# electric-imp-version.net
KiCad netlist of a schematic drawn in EAGLE
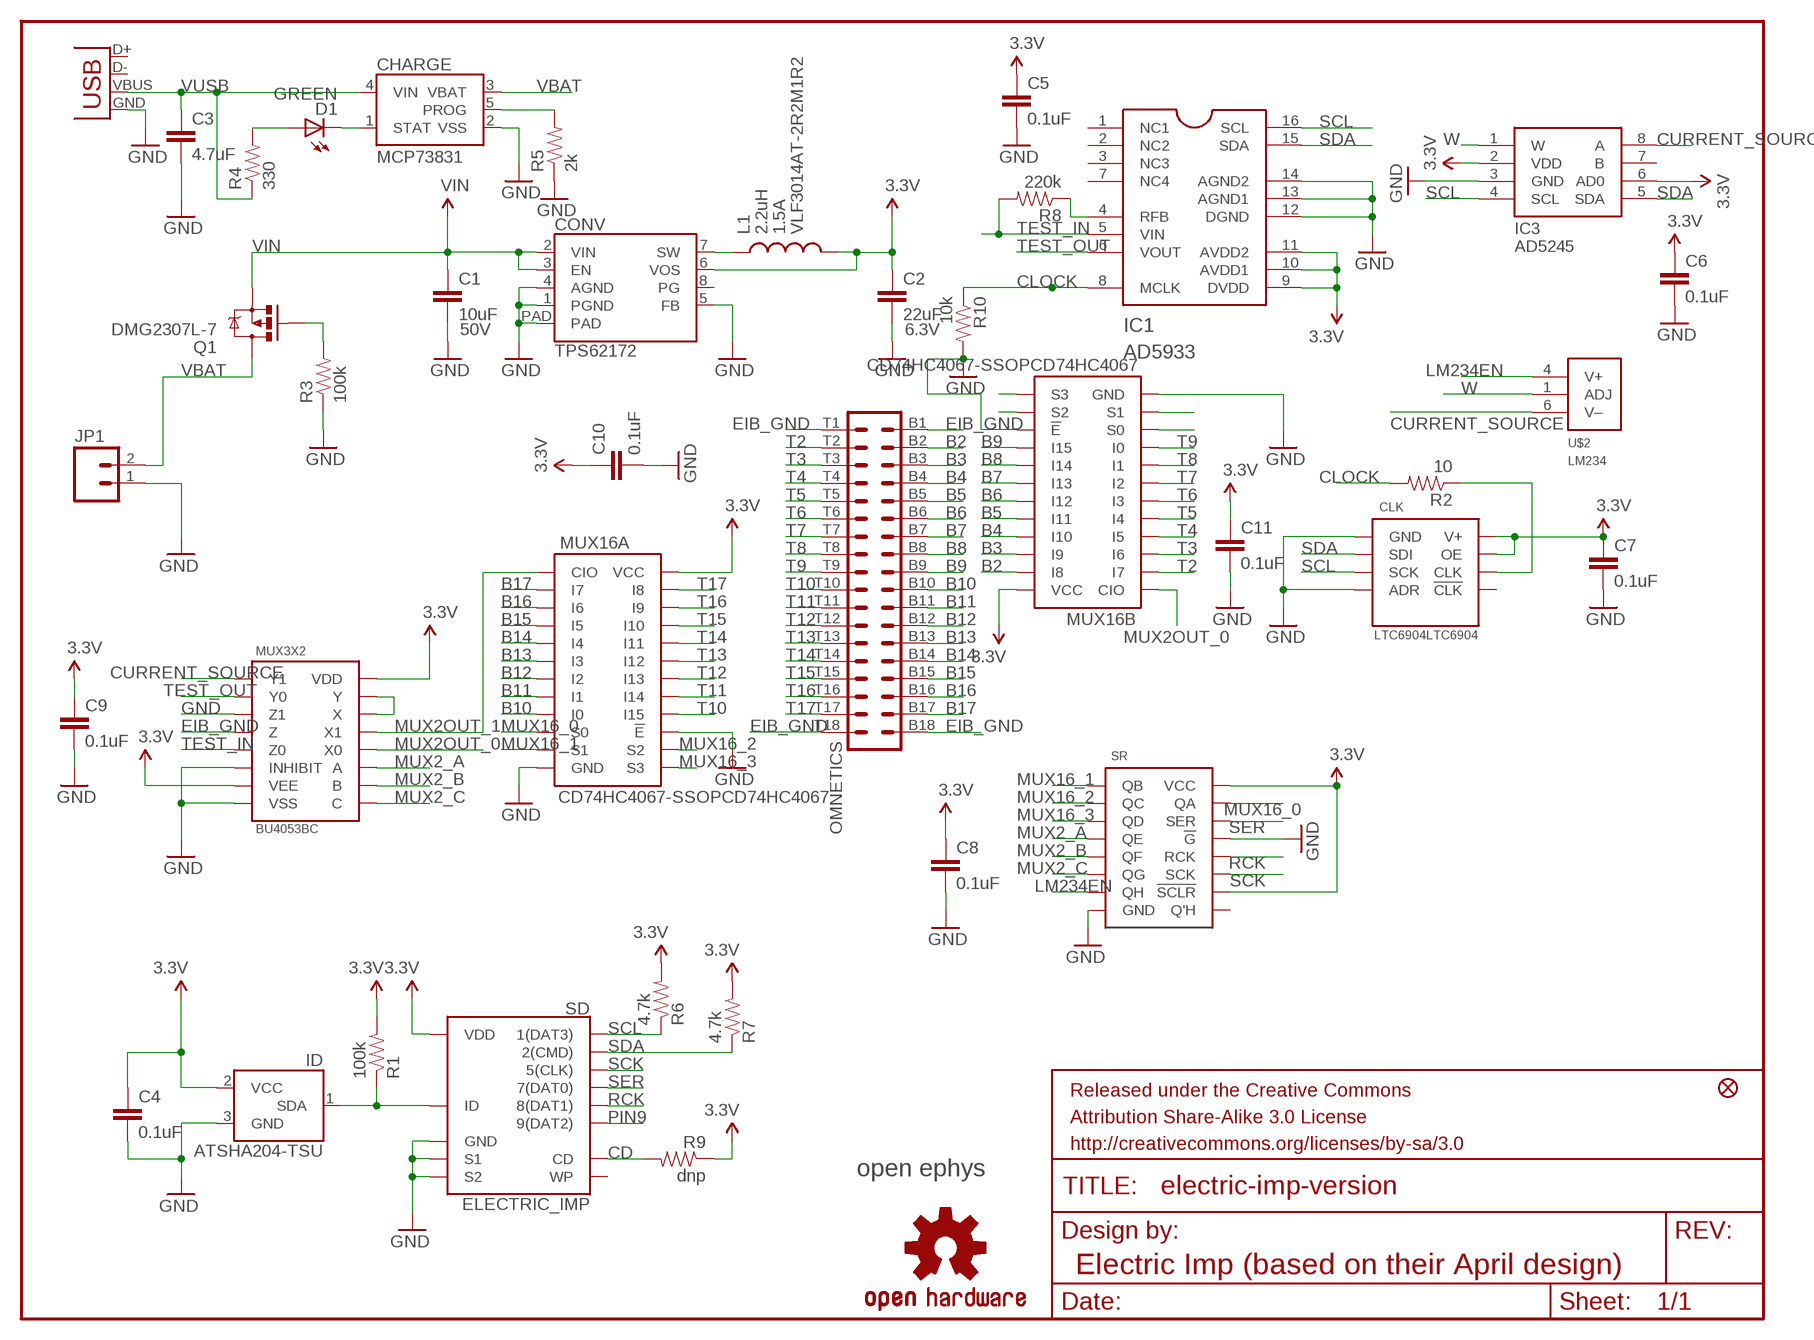
[diagram p0: schematic, sheet 1]

(export (version "E")
  (design (tool "Eeschema 10.0.6"))
  (components
    (comp (ref "C1")
      (value "10uF")
      (footprint "eagle-import:1210")
      (libsource (lib "eagle-import") (part "SparkFun-Passives_CAP1210"))
    )
    (comp (ref "C2")
      (value "22uF")
      (footprint "eagle-import:0805")
      (libsource (lib "eagle-import") (part "SparkFun-Passives_CAP0805"))
    )
    (comp (ref "C3")
      (value "4.7uF")
      (footprint "eagle-import:1210")
      (libsource (lib "eagle-import") (part "SparkFun-Passives_CAP1210"))
    )
    (comp (ref "C4")
      (value "0.1uF")
      (footprint "eagle-import:0603-CAP")
      (libsource (lib "eagle-import") (part "CAP0603-CAP"))
    )
    (comp (ref "C5")
      (value "0.1uF")
      (footprint "eagle-import:0603-CAP")
      (libsource (lib "eagle-import") (part "CAP0603-CAP"))
    )
    (comp (ref "C6")
      (value "0.1uF")
      (footprint "eagle-import:0603-CAP")
      (libsource (lib "eagle-import") (part "CAP0603-CAP"))
    )
    (comp (ref "C7")
      (value "0.1uF")
      (footprint "eagle-import:0603-CAP")
      (libsource (lib "eagle-import") (part "CAP0603-CAP"))
    )
    (comp (ref "C8")
      (value "0.1uF")
      (footprint "eagle-import:0603-CAP")
      (libsource (lib "eagle-import") (part "CAP0603-CAP"))
    )
    (comp (ref "C9")
      (value "0.1uF")
      (footprint "eagle-import:0603-CAP")
      (libsource (lib "eagle-import") (part "CAP0603-CAP"))
    )
    (comp (ref "C10")
      (value "0.1uF")
      (footprint "eagle-import:0603-CAP")
      (libsource (lib "eagle-import") (part "CAP0603-CAP"))
    )
    (comp (ref "C11")
      (value "0.1uF")
      (footprint "eagle-import:0603-CAP")
      (libsource (lib "eagle-import") (part "CAP0603-CAP"))
    )
    (comp (ref "CHARGE")
      (value "MCP73831")
      (footprint "eagle-import:SOT23-5")
      (libsource (lib "eagle-import") (part "MCP73831"))
    )
    (comp (ref "CLK")
      (value "LTC6904LTC6904")
      (footprint "eagle-import:MSOP08")
      (libsource (lib "eagle-import") (part "LTC6904LTC6904"))
    )
    (comp (ref "CONV")
      (value "TPS62172")
      (footprint "eagle-import:WSON-8-PAD")
      (libsource (lib "eagle-import") (part "TPS62172"))
    )
    (comp (ref "D1")
      (value "GREEN")
      (footprint "eagle-import:LED-0603")
      (libsource (lib "eagle-import") (part "LED-GREEN0603"))
    )
    (comp (ref "FRAME1")
      (value "FRAME-LETTER")
      (footprint "eagle-import:CREATIVE_COMMONS")
      (libsource (lib "eagle-import") (part "FRAME-LETTER"))
    )
    (comp (ref "IC1")
      (value "AD5933")
      (footprint "eagle-import:AD5933")
      (libsource (lib "eagle-import") (part "AD5933"))
    )
    (comp (ref "IC3")
      (value "AD5245")
      (footprint "eagle-import:AD5245")
      (libsource (lib "eagle-import") (part "AD5245"))
    )
    (comp (ref "ID")
      (value "ATSHA204-TSU")
      (footprint "eagle-import:SOT23-3")
      (libsource (lib "eagle-import") (part "ATSHA204-TSU"))
    )
    (comp (ref "JP1")
      (value "M02SMD")
      (footprint "eagle-import:1X02_SMD")
      (libsource (lib "eagle-import") (part "M02SMD"))
    )
    (comp (ref "JP8")
      (value "FIDUCIALUFIDUCIAL")
      (footprint "eagle-import:MICRO-FIDUCIAL")
      (libsource (lib "eagle-import") (part "FIDUCIALUFIDUCIAL"))
    )
    (comp (ref "L1")
      (value "2.2uH")
      (footprint "eagle-import:VLF4012A")
      (libsource (lib "eagle-import") (part "INDUCTORVLF4012A"))
    )
    (comp (ref "MUX3X2")
      (value "BU4053BC")
      (footprint "eagle-import:SSOP16")
      (libsource (lib "eagle-import") (part "BU4053BC"))
    )
    (comp (ref "MUX16A")
      (value "CD74HC4067-SSOPCD74HC4067")
      (footprint "eagle-import:SSOP24")
      (libsource (lib "eagle-import") (part "CD74HC4067-SSOPCD74HC4067"))
    )
    (comp (ref "MUX16B")
      (value "CD74HC4067-SSOPCD74HC4067")
      (footprint "eagle-import:SSOP24")
      (libsource (lib "eagle-import") (part "CD74HC4067-SSOPCD74HC4067"))
    )
    (comp (ref "OMNETICS")
      (value "OMNETICS_A79025")
      (footprint "eagle-import:OMNETICS_A79025")
      (libsource (lib "eagle-import") (part "OMNETICS_A79025"))
    )
    (comp (ref "Q1")
      (value "DMG2307L-7")
      (footprint "eagle-import:SOT23-3")
      (libsource (lib "eagle-import") (part "MOSFET-PCHANNELSMD"))
    )
    (comp (ref "R1")
      (value "100k")
      (footprint "eagle-import:0402-RES")
      (libsource (lib "eagle-import") (part "RESISTOR0402-RES"))
    )
    (comp (ref "R2")
      (value "10")
      (footprint "eagle-import:0402-RES")
      (libsource (lib "eagle-import") (part "RESISTOR0402-RES"))
    )
    (comp (ref "R3")
      (value "100k")
      (footprint "eagle-import:0402-RES")
      (libsource (lib "eagle-import") (part "RESISTOR0402-RES"))
    )
    (comp (ref "R4")
      (value "330")
      (footprint "eagle-import:0402-RES")
      (libsource (lib "eagle-import") (part "RESISTOR0402-RES"))
    )
    (comp (ref "R5")
      (value "2k")
      (footprint "eagle-import:0402-RES")
      (libsource (lib "eagle-import") (part "RESISTOR0402-RES"))
    )
    (comp (ref "R6")
      (value "4.7k")
      (footprint "eagle-import:0402-RES")
      (libsource (lib "eagle-import") (part "RESISTOR0402-RES"))
    )
    (comp (ref "R7")
      (value "4.7k")
      (footprint "eagle-import:0402-RES")
      (libsource (lib "eagle-import") (part "RESISTOR0402-RES"))
    )
    (comp (ref "R8")
      (value "220k")
      (footprint "eagle-import:0402-RES")
      (libsource (lib "eagle-import") (part "RESISTOR0402-RES"))
    )
    (comp (ref "R9")
      (value "dnp")
      (footprint "eagle-import:0402-RES")
      (libsource (lib "eagle-import") (part "RESISTOR0402-RES"))
    )
    (comp (ref "R10")
      (value "10k")
      (footprint "eagle-import:0402-RES")
      (libsource (lib "eagle-import") (part "RESISTOR0402-RES"))
    )
    (comp (ref "SD")
      (value "ELECTRIC_IMP")
      (footprint "eagle-import:SD_MMC_SOCKET")
      (libsource (lib "eagle-import") (part "ELECTRIC_IMP"))
    )
    (comp (ref "SR")
      (value "MM74HC595MM74HC595")
      (footprint "eagle-import:TSSOP16")
      (libsource (lib "eagle-import") (part "MM74HC595MM74HC595"))
    )
    (comp (ref "U$2")
      (value "LM234")
      (footprint "eagle-import:LM234")
      (libsource (lib "eagle-import") (part "LM234"))
    )
    (comp (ref "U$5")
      (value "OSHW-LOGOS")
      (footprint "eagle-import:OSHW-LOGO-S")
      (libsource (lib "eagle-import") (part "OSHW-LOGOS"))
    )
    (comp (ref "U$7")
      (value "OPEN_EPHYS_LOGO")
      (footprint "eagle-import:OPEN_EPHYS_LOGO")
      (libsource (lib "eagle-import") (part "OPEN_EPHYS_LOGO"))
    )
    (comp (ref "USB")
      (value "USBSMD")
      (footprint "eagle-import:USB-MINIB")
      (libsource (lib "eagle-import") (part "USBSMD"))
    )
  )
  (nets
    (net (code "1") (name "/B2") (class "Default")
      (node (ref "MUX16B") (pin "23") (pinfunction "I8_23") (pintype "bidirectional"))
      (node (ref "OMNETICS") (pin "B2") (pinfunction "B2_B2") (pintype "passive"))
    )
    (net (code "2") (name "/B3") (class "Default")
      (node (ref "MUX16B") (pin "22") (pinfunction "I9_22") (pintype "bidirectional"))
      (node (ref "OMNETICS") (pin "B3") (pinfunction "B3_B3") (pintype "passive"))
    )
    (net (code "3") (name "/B4") (class "Default")
      (node (ref "MUX16B") (pin "21") (pinfunction "I10_21") (pintype "bidirectional"))
      (node (ref "OMNETICS") (pin "B4") (pinfunction "B4_B4") (pintype "passive"))
    )
    (net (code "4") (name "/B5") (class "Default")
      (node (ref "MUX16B") (pin "20") (pinfunction "I11_20") (pintype "bidirectional"))
      (node (ref "OMNETICS") (pin "B5") (pinfunction "B5_B5") (pintype "passive"))
    )
    (net (code "5") (name "/B6") (class "Default")
      (node (ref "MUX16B") (pin "19") (pinfunction "I12_19") (pintype "bidirectional"))
      (node (ref "OMNETICS") (pin "B6") (pinfunction "B6_B6") (pintype "passive"))
    )
    (net (code "6") (name "/B7") (class "Default")
      (node (ref "MUX16B") (pin "18") (pinfunction "I13_18") (pintype "bidirectional"))
      (node (ref "OMNETICS") (pin "B7") (pinfunction "B7_B7") (pintype "passive"))
    )
    (net (code "7") (name "/B8") (class "Default")
      (node (ref "MUX16B") (pin "17") (pinfunction "I14_17") (pintype "bidirectional"))
      (node (ref "OMNETICS") (pin "B8") (pinfunction "B8_B8") (pintype "passive"))
    )
    (net (code "8") (name "/B9") (class "Default")
      (node (ref "MUX16B") (pin "16") (pinfunction "I15_16") (pintype "bidirectional"))
      (node (ref "OMNETICS") (pin "B9") (pinfunction "B9_B9") (pintype "passive"))
    )
    (net (code "9") (name "/B10") (class "Default")
      (node (ref "MUX16A") (pin "9") (pinfunction "I0_9") (pintype "bidirectional"))
      (node (ref "OMNETICS") (pin "B10") (pinfunction "B10_B10") (pintype "passive"))
    )
    (net (code "10") (name "/B11") (class "Default")
      (node (ref "MUX16A") (pin "8") (pinfunction "I1_8") (pintype "bidirectional"))
      (node (ref "OMNETICS") (pin "B11") (pinfunction "B11_B11") (pintype "passive"))
    )
    (net (code "11") (name "/B12") (class "Default")
      (node (ref "MUX16A") (pin "7") (pinfunction "I2_7") (pintype "bidirectional"))
      (node (ref "OMNETICS") (pin "B12") (pinfunction "B12_B12") (pintype "passive"))
    )
    (net (code "12") (name "/B13") (class "Default")
      (node (ref "MUX16A") (pin "6") (pinfunction "I3_6") (pintype "bidirectional"))
      (node (ref "OMNETICS") (pin "B13") (pinfunction "B13_B13") (pintype "passive"))
    )
    (net (code "13") (name "/B14") (class "Default")
      (node (ref "MUX16A") (pin "5") (pinfunction "I4_5") (pintype "bidirectional"))
      (node (ref "OMNETICS") (pin "B14") (pinfunction "B14_B14") (pintype "passive"))
    )
    (net (code "14") (name "/B15") (class "Default")
      (node (ref "MUX16A") (pin "4") (pinfunction "I5_4") (pintype "bidirectional"))
      (node (ref "OMNETICS") (pin "B15") (pinfunction "B15_B15") (pintype "passive"))
    )
    (net (code "15") (name "/B16") (class "Default")
      (node (ref "MUX16A") (pin "3") (pinfunction "I6_3") (pintype "bidirectional"))
      (node (ref "OMNETICS") (pin "B16") (pinfunction "B16_B16") (pintype "passive"))
    )
    (net (code "16") (name "/B17") (class "Default")
      (node (ref "MUX16A") (pin "2") (pinfunction "I7_2") (pintype "bidirectional"))
      (node (ref "OMNETICS") (pin "B17") (pinfunction "B17_B17") (pintype "passive"))
    )
    (net (code "17") (name "/CD") (class "Default")
      (node (ref "R9") (pin "2") (pinfunction "2_2") (pintype "passive"))
      (node (ref "SD") (pin "CD") (pinfunction "CD_CD") (pintype "bidirectional"))
    )
    (net (code "18") (name "/CLOCK") (class "Default")
      (node (ref "IC1") (pin "8") (pinfunction "MCLK_8") (pintype "bidirectional"))
      (node (ref "R10") (pin "1") (pinfunction "1_1") (pintype "passive"))
      (node (ref "R2") (pin "2") (pinfunction "2_2") (pintype "passive"))
    )
    (net (code "19") (name "/CURRENT_SOURCE") (class "Default")
      (node (ref "IC3") (pin "8") (pinfunction "A_8") (pintype "bidirectional"))
      (node (ref "MUX3X2") (pin "1") (pinfunction "Y1_1") (pintype "bidirectional"))
      (node (ref "U$2") (pin "6") (pinfunction "V–_6") (pintype "bidirectional"))
    )
    (net (code "20") (name "/EIB_GND") (class "Default")
      (node (ref "MUX3X2") (pin "4") (pinfunction "Z_4") (pintype "bidirectional"))
      (node (ref "OMNETICS") (pin "B1") (pinfunction "B1_B1") (pintype "passive"))
      (node (ref "OMNETICS") (pin "B18") (pinfunction "B18_B18") (pintype "passive"))
      (node (ref "OMNETICS") (pin "T1") (pinfunction "T1_T1") (pintype "passive"))
      (node (ref "OMNETICS") (pin "T18") (pinfunction "T18_T18") (pintype "passive"))
    )
    (net (code "21") (name "/LM234EN") (class "Default")
      (node (ref "SR") (pin "7") (pinfunction "QH_7") (pintype "output"))
      (node (ref "U$2") (pin "4") (pinfunction "V+_4") (pintype "bidirectional"))
    )
    (net (code "22") (name "/MUX2OUT_0") (class "Default")
      (node (ref "MUX16B") (pin "1") (pinfunction "CIO_1") (pintype "bidirectional"))
      (node (ref "MUX3X2") (pin "12") (pinfunction "X0_12") (pintype "bidirectional"))
    )
    (net (code "23") (name "/MUX2OUT_1") (class "Default")
      (node (ref "MUX16A") (pin "1") (pinfunction "CIO_1") (pintype "bidirectional"))
      (node (ref "MUX3X2") (pin "13") (pinfunction "X1_13") (pintype "bidirectional"))
    )
    (net (code "24") (name "/MUX2_A") (class "Default")
      (node (ref "MUX3X2") (pin "11") (pinfunction "A_11") (pintype "bidirectional"))
      (node (ref "SR") (pin "4") (pinfunction "QE_4") (pintype "output"))
    )
    (net (code "25") (name "/MUX2_B") (class "Default")
      (node (ref "MUX3X2") (pin "10") (pinfunction "B_10") (pintype "bidirectional"))
      (node (ref "SR") (pin "5") (pinfunction "QF_5") (pintype "output"))
    )
    (net (code "26") (name "/MUX2_C") (class "Default")
      (node (ref "MUX3X2") (pin "9") (pinfunction "C_9") (pintype "power_in"))
      (node (ref "SR") (pin "6") (pinfunction "QG_6") (pintype "output"))
    )
    (net (code "27") (name "/MUX16_0") (class "Default")
      (node (ref "MUX16A") (pin "10") (pinfunction "S0_10") (pintype "bidirectional"))
      (node (ref "MUX16B") (pin "10") (pinfunction "S0_10") (pintype "bidirectional"))
      (node (ref "SR") (pin "15") (pinfunction "QA_15") (pintype "output"))
    )
    (net (code "28") (name "/MUX16_1") (class "Default")
      (node (ref "MUX16A") (pin "11") (pinfunction "S1_11") (pintype "bidirectional"))
      (node (ref "MUX16B") (pin "11") (pinfunction "S1_11") (pintype "bidirectional"))
      (node (ref "SR") (pin "1") (pinfunction "QB_1") (pintype "output"))
    )
    (net (code "29") (name "/MUX16_2") (class "Default")
      (node (ref "MUX16A") (pin "14") (pinfunction "S2_14") (pintype "bidirectional"))
      (node (ref "MUX16B") (pin "14") (pinfunction "S2_14") (pintype "bidirectional"))
      (node (ref "SR") (pin "2") (pinfunction "QC_2") (pintype "output"))
    )
    (net (code "30") (name "/MUX16_3") (class "Default")
      (node (ref "MUX16A") (pin "13") (pinfunction "S3_13") (pintype "bidirectional"))
      (node (ref "MUX16B") (pin "13") (pinfunction "S3_13") (pintype "bidirectional"))
      (node (ref "SR") (pin "3") (pinfunction "QD_3") (pintype "output"))
    )
    (net (code "31") (name "/PIN9") (class "Default")
      (node (ref "SD") (pin "9") (pinfunction "9(DAT2)_9") (pintype "bidirectional"))
    )
    (net (code "32") (name "/RCK") (class "Default")
      (node (ref "SD") (pin "8") (pinfunction "8(DAT1)_8") (pintype "bidirectional"))
      (node (ref "SR") (pin "12") (pinfunction "RCK_12") (pintype "input"))
    )
    (net (code "33") (name "/SCK") (class "Default")
      (node (ref "SD") (pin "5") (pinfunction "5(CLK)_5") (pintype "bidirectional"))
      (node (ref "SR") (pin "11") (pinfunction "SCK_11") (pintype "input"))
    )
    (net (code "34") (name "/SCL") (class "Default")
      (node (ref "CLK") (pin "3") (pinfunction "SCK_3") (pintype "input"))
      (node (ref "IC1") (pin "16") (pinfunction "SCL_16") (pintype "bidirectional"))
      (node (ref "IC3") (pin "4") (pinfunction "SCL_4") (pintype "bidirectional"))
      (node (ref "R6") (pin "1") (pinfunction "1_1") (pintype "passive"))
      (node (ref "SD") (pin "1") (pinfunction "1(DAT3)_1") (pintype "bidirectional"))
    )
    (net (code "35") (name "/SDA") (class "Default")
      (node (ref "CLK") (pin "2") (pinfunction "SDI_2") (pintype "input"))
      (node (ref "IC1") (pin "15") (pinfunction "SDA_15") (pintype "bidirectional"))
      (node (ref "IC3") (pin "5") (pinfunction "SDA_5") (pintype "bidirectional"))
      (node (ref "R7") (pin "1") (pinfunction "1_1") (pintype "passive"))
      (node (ref "SD") (pin "2") (pinfunction "2(CMD)_2") (pintype "bidirectional"))
    )
    (net (code "36") (name "/SER") (class "Default")
      (node (ref "SD") (pin "7") (pinfunction "7(DAT0)_7") (pintype "bidirectional"))
      (node (ref "SR") (pin "14") (pinfunction "SER_14") (pintype "input"))
    )
    (net (code "37") (name "/T2") (class "Default")
      (node (ref "MUX16B") (pin "2") (pinfunction "I7_2") (pintype "bidirectional"))
      (node (ref "OMNETICS") (pin "T2") (pinfunction "T2_T2") (pintype "passive"))
    )
    (net (code "38") (name "/T3") (class "Default")
      (node (ref "MUX16B") (pin "3") (pinfunction "I6_3") (pintype "bidirectional"))
      (node (ref "OMNETICS") (pin "T3") (pinfunction "T3_T3") (pintype "passive"))
    )
    (net (code "39") (name "/T4") (class "Default")
      (node (ref "MUX16B") (pin "4") (pinfunction "I5_4") (pintype "bidirectional"))
      (node (ref "OMNETICS") (pin "T4") (pinfunction "T4_T4") (pintype "passive"))
    )
    (net (code "40") (name "/T5") (class "Default")
      (node (ref "MUX16B") (pin "5") (pinfunction "I4_5") (pintype "bidirectional"))
      (node (ref "OMNETICS") (pin "T5") (pinfunction "T5_T5") (pintype "passive"))
    )
    (net (code "41") (name "/T6") (class "Default")
      (node (ref "MUX16B") (pin "6") (pinfunction "I3_6") (pintype "bidirectional"))
      (node (ref "OMNETICS") (pin "T6") (pinfunction "T6_T6") (pintype "passive"))
    )
    (net (code "42") (name "/T7") (class "Default")
      (node (ref "MUX16B") (pin "7") (pinfunction "I2_7") (pintype "bidirectional"))
      (node (ref "OMNETICS") (pin "T7") (pinfunction "T7_T7") (pintype "passive"))
    )
    (net (code "43") (name "/T8") (class "Default")
      (node (ref "MUX16B") (pin "8") (pinfunction "I1_8") (pintype "bidirectional"))
      (node (ref "OMNETICS") (pin "T8") (pinfunction "T8_T8") (pintype "passive"))
    )
    (net (code "44") (name "/T9") (class "Default")
      (node (ref "MUX16B") (pin "9") (pinfunction "I0_9") (pintype "bidirectional"))
      (node (ref "OMNETICS") (pin "T9") (pinfunction "T9_T9") (pintype "passive"))
    )
    (net (code "45") (name "/T10") (class "Default")
      (node (ref "MUX16A") (pin "16") (pinfunction "I15_16") (pintype "bidirectional"))
      (node (ref "OMNETICS") (pin "T10") (pinfunction "T10_T10") (pintype "passive"))
    )
    (net (code "46") (name "/T11") (class "Default")
      (node (ref "MUX16A") (pin "17") (pinfunction "I14_17") (pintype "bidirectional"))
      (node (ref "OMNETICS") (pin "T11") (pinfunction "T11_T11") (pintype "passive"))
    )
    (net (code "47") (name "/T12") (class "Default")
      (node (ref "MUX16A") (pin "18") (pinfunction "I13_18") (pintype "bidirectional"))
      (node (ref "OMNETICS") (pin "T12") (pinfunction "T12_T12") (pintype "passive"))
    )
    (net (code "48") (name "/T13") (class "Default")
      (node (ref "MUX16A") (pin "19") (pinfunction "I12_19") (pintype "bidirectional"))
      (node (ref "OMNETICS") (pin "T13") (pinfunction "T13_T13") (pintype "passive"))
    )
    (net (code "49") (name "/T14") (class "Default")
      (node (ref "MUX16A") (pin "20") (pinfunction "I11_20") (pintype "bidirectional"))
      (node (ref "OMNETICS") (pin "T14") (pinfunction "T14_T14") (pintype "passive"))
    )
    (net (code "50") (name "/T15") (class "Default")
      (node (ref "MUX16A") (pin "21") (pinfunction "I10_21") (pintype "bidirectional"))
      (node (ref "OMNETICS") (pin "T15") (pinfunction "T15_T15") (pintype "passive"))
    )
    (net (code "51") (name "/T16") (class "Default")
      (node (ref "MUX16A") (pin "22") (pinfunction "I9_22") (pintype "bidirectional"))
      (node (ref "OMNETICS") (pin "T16") (pinfunction "T16_T16") (pintype "passive"))
    )
    (net (code "52") (name "/T17") (class "Default")
      (node (ref "MUX16A") (pin "23") (pinfunction "I8_23") (pintype "bidirectional"))
      (node (ref "OMNETICS") (pin "T17") (pinfunction "T17_T17") (pintype "passive"))
    )
    (net (code "53") (name "/TEST_IN") (class "Default")
      (node (ref "IC1") (pin "5") (pinfunction "VIN_5") (pintype "bidirectional"))
      (node (ref "MUX3X2") (pin "5") (pinfunction "Z0_5") (pintype "bidirectional"))
      (node (ref "R8") (pin "2") (pinfunction "2_2") (pintype "passive"))
    )
    (net (code "54") (name "/TEST_OUT") (class "Default")
      (node (ref "IC1") (pin "6") (pinfunction "VOUT_6") (pintype "bidirectional"))
      (node (ref "MUX3X2") (pin "2") (pinfunction "Y0_2") (pintype "bidirectional"))
    )
    (net (code "55") (name "/VBAT") (class "Default")
      (node (ref "CHARGE") (pin "3") (pinfunction "VBAT_3") (pintype "power_in"))
      (node (ref "JP1") (pin "2") (pinfunction "2_2") (pintype "passive"))
      (node (ref "Q1") (pin "3") (pinfunction "D_3") (pintype "passive"))
    )
    (net (code "56") (name "/VUSB") (class "Default")
      (node (ref "C3") (pin "1") (pinfunction "1_1") (pintype "passive"))
      (node (ref "CHARGE") (pin "4") (pinfunction "VIN_4") (pintype "power_in"))
      (node (ref "R4") (pin "1") (pinfunction "1_1") (pintype "passive"))
      (node (ref "USB") (pin "VBUS") (pinfunction "VBUS_VBUS") (pintype "bidirectional"))
    )
    (net (code "57") (name "/W") (class "Default")
      (node (ref "IC3") (pin "1") (pinfunction "W_1") (pintype "bidirectional"))
      (node (ref "U$2") (pin "1") (pinfunction "ADJ_1") (pintype "bidirectional"))
    )
    (net (code "58") (name "3.3V") (class "Default")
      (node (ref "C10") (pin "1") (pinfunction "1_1") (pintype "passive"))
      (node (ref "C11") (pin "1") (pinfunction "1_1") (pintype "passive"))
      (node (ref "C2") (pin "1") (pinfunction "1_1") (pintype "passive"))
      (node (ref "C4") (pin "1") (pinfunction "1_1") (pintype "passive"))
      (node (ref "C5") (pin "1") (pinfunction "1_1") (pintype "passive"))
      (node (ref "C6") (pin "1") (pinfunction "1_1") (pintype "passive"))
      (node (ref "C7") (pin "1") (pinfunction "1_1") (pintype "passive"))
      (node (ref "C8") (pin "1") (pinfunction "1_1") (pintype "passive"))
      (node (ref "C9") (pin "1") (pinfunction "1_1") (pintype "passive"))
      (node (ref "CLK") (pin "7") (pinfunction "OE_7") (pintype "bidirectional"))
      (node (ref "CLK") (pin "8") (pinfunction "V+_8") (pintype "power_in"))
      (node (ref "CONV") (pin "6") (pinfunction "VOS_6") (pintype "bidirectional"))
      (node (ref "IC1") (pin "10") (pinfunction "AVDD1_10") (pintype "bidirectional"))
      (node (ref "IC1") (pin "11") (pinfunction "AVDD2_11") (pintype "bidirectional"))
      (node (ref "IC1") (pin "9") (pinfunction "DVDD_9") (pintype "bidirectional"))
      (node (ref "IC3") (pin "2") (pinfunction "VDD_2") (pintype "bidirectional"))
      (node (ref "IC3") (pin "6") (pinfunction "AD0_6") (pintype "bidirectional"))
      (node (ref "ID") (pin "2") (pinfunction "VCC_2") (pintype "bidirectional"))
      (node (ref "L1") (pin "P$2") (pinfunction "2_P$2") (pintype "passive"))
      (node (ref "MUX16A") (pin "24") (pinfunction "VCC_24") (pintype "power_in"))
      (node (ref "MUX16B") (pin "24") (pinfunction "VCC_24") (pintype "power_in"))
      (node (ref "MUX3X2") (pin "16") (pinfunction "VDD_16") (pintype "input"))
      (node (ref "MUX3X2") (pin "7") (pinfunction "VEE_7") (pintype "power_in"))
      (node (ref "R1") (pin "2") (pinfunction "2_2") (pintype "passive"))
      (node (ref "R6") (pin "2") (pinfunction "2_2") (pintype "passive"))
      (node (ref "R7") (pin "2") (pinfunction "2_2") (pintype "passive"))
      (node (ref "R9") (pin "1") (pinfunction "1_1") (pintype "passive"))
      (node (ref "SD") (pin "4") (pinfunction "VDD_4") (pintype "bidirectional"))
      (node (ref "SR") (pin "10") (pinfunction "~{SCLR}_10") (pintype "bidirectional"))
      (node (ref "SR") (pin "16") (pinfunction "VCC_16") (pintype "power_in"))
    )
    (net (code "59") (name "GND") (class "Default")
      (node (ref "C1") (pin "2") (pinfunction "2_2") (pintype "passive"))
      (node (ref "C10") (pin "2") (pinfunction "2_2") (pintype "passive"))
      (node (ref "C11") (pin "2") (pinfunction "2_2") (pintype "passive"))
      (node (ref "C2") (pin "2") (pinfunction "2_2") (pintype "passive"))
      (node (ref "C3") (pin "2") (pinfunction "2_2") (pintype "passive"))
      (node (ref "C4") (pin "2") (pinfunction "2_2") (pintype "passive"))
      (node (ref "C5") (pin "2") (pinfunction "2_2") (pintype "passive"))
      (node (ref "C6") (pin "2") (pinfunction "2_2") (pintype "passive"))
      (node (ref "C7") (pin "2") (pinfunction "2_2") (pintype "passive"))
      (node (ref "C8") (pin "2") (pinfunction "2_2") (pintype "passive"))
      (node (ref "C9") (pin "2") (pinfunction "2_2") (pintype "passive"))
      (node (ref "CHARGE") (pin "2") (pinfunction "VSS_2") (pintype "power_in"))
      (node (ref "CLK") (pin "1") (pinfunction "GND_1") (pintype "power_in"))
      (node (ref "CLK") (pin "4") (pinfunction "ADR_4") (pintype "bidirectional"))
      (node (ref "CONV") (pin "1") (pinfunction "PGND_1") (pintype "bidirectional"))
      (node (ref "CONV") (pin "4") (pinfunction "AGND_4") (pintype "bidirectional"))
      (node (ref "CONV") (pin "5") (pinfunction "FB_5") (pintype "bidirectional"))
      (node (ref "CONV") (pin "PAD") (pinfunction "PAD_PAD") (pintype "bidirectional"))
      (node (ref "IC1") (pin "12") (pinfunction "DGND_12") (pintype "bidirectional"))
      (node (ref "IC1") (pin "13") (pinfunction "AGND1_13") (pintype "bidirectional"))
      (node (ref "IC1") (pin "14") (pinfunction "AGND2_14") (pintype "bidirectional"))
      (node (ref "IC3") (pin "3") (pinfunction "GND_3") (pintype "bidirectional"))
      (node (ref "ID") (pin "3") (pinfunction "GND_3") (pintype "bidirectional"))
      (node (ref "JP1") (pin "1") (pinfunction "1_1") (pintype "passive"))
      (node (ref "MUX16A") (pin "12") (pinfunction "GND_12") (pintype "power_in"))
      (node (ref "MUX16A") (pin "15") (pinfunction "~{E}_15") (pintype "bidirectional"))
      (node (ref "MUX16B") (pin "12") (pinfunction "GND_12") (pintype "power_in"))
      (node (ref "MUX16B") (pin "15") (pinfunction "~{E}_15") (pintype "bidirectional"))
      (node (ref "MUX3X2") (pin "3") (pinfunction "Z1_3") (pintype "bidirectional"))
      (node (ref "MUX3X2") (pin "6") (pinfunction "INHIBIT_6") (pintype "bidirectional"))
      (node (ref "MUX3X2") (pin "8") (pinfunction "VSS_8") (pintype "power_in"))
      (node (ref "R10") (pin "2") (pinfunction "2_2") (pintype "passive"))
      (node (ref "R3") (pin "1") (pinfunction "1_1") (pintype "passive"))
      (node (ref "R5") (pin "1") (pinfunction "1_1") (pintype "passive"))
      (node (ref "SD") (pin "3") (pinfunction "GND_3") (pintype "bidirectional"))
      (node (ref "SD") (pin "S1") (pinfunction "S1_S1") (pintype "bidirectional"))
      (node (ref "SD") (pin "S2") (pinfunction "S2_S2") (pintype "bidirectional"))
      (node (ref "SR") (pin "13") (pinfunction "~{G}_13") (pintype "bidirectional"))
      (node (ref "SR") (pin "8") (pinfunction "GND_8") (pintype "power_in"))
      (node (ref "USB") (pin "GND") (pinfunction "GND_GND") (pintype "bidirectional"))
    )
    (net (code "60") (name "Net-(CHARGE-PROG)") (class "Default")
      (node (ref "CHARGE") (pin "5") (pinfunction "PROG_5") (pintype "input"))
      (node (ref "R5") (pin "2") (pinfunction "2_2") (pintype "passive"))
    )
    (net (code "61") (name "Net-(CHARGE-STAT)") (class "Default")
      (node (ref "CHARGE") (pin "1") (pinfunction "STAT_1") (pintype "output"))
      (node (ref "D1") (pin "C") (pinfunction "C_C") (pintype "passive"))
    )
    (net (code "62") (name "Net-(CLK-CLK)") (class "Default")
      (node (ref "CLK") (pin "6") (pinfunction "CLK_6") (pintype "output"))
      (node (ref "R2") (pin "1") (pinfunction "1_1") (pintype "passive"))
    )
    (net (code "63") (name "Net-(CONV-SW)") (class "Default")
      (node (ref "CONV") (pin "7") (pinfunction "SW_7") (pintype "bidirectional"))
      (node (ref "L1") (pin "P$1") (pinfunction "1_P$1") (pintype "passive"))
    )
    (net (code "64") (name "Net-(D1-PadA)") (class "Default")
      (node (ref "D1") (pin "A") (pinfunction "A_A") (pintype "passive"))
      (node (ref "R4") (pin "2") (pinfunction "2_2") (pintype "passive"))
    )
    (net (code "65") (name "Net-(IC1-RFB)") (class "Default")
      (node (ref "IC1") (pin "4") (pinfunction "RFB_4") (pintype "bidirectional"))
      (node (ref "R8") (pin "1") (pinfunction "1_1") (pintype "passive"))
    )
    (net (code "66") (name "Net-(ID-SDA)") (class "Default")
      (node (ref "ID") (pin "1") (pinfunction "SDA_1") (pintype "bidirectional"))
      (node (ref "R1") (pin "1") (pinfunction "1_1") (pintype "passive"))
      (node (ref "SD") (pin "6") (pinfunction "ID_6") (pintype "bidirectional"))
    )
    (net (code "67") (name "Net-(MUX3X2-X)") (class "Default")
      (node (ref "MUX3X2") (pin "14") (pinfunction "X_14") (pintype "bidirectional"))
      (node (ref "MUX3X2") (pin "15") (pinfunction "Y_15") (pintype "bidirectional"))
    )
    (net (code "68") (name "Net-(Q1-G)") (class "Default")
      (node (ref "Q1") (pin "1") (pinfunction "G_1") (pintype "passive"))
      (node (ref "R3") (pin "2") (pinfunction "2_2") (pintype "passive"))
    )
    (net (code "69") (name "VIN") (class "Default")
      (node (ref "C1") (pin "1") (pinfunction "1_1") (pintype "passive"))
      (node (ref "CONV") (pin "2") (pinfunction "VIN_2") (pintype "bidirectional"))
      (node (ref "CONV") (pin "3") (pinfunction "EN_3") (pintype "bidirectional"))
      (node (ref "Q1") (pin "2") (pinfunction "S_2") (pintype "passive"))
    )
    (net (code "70") (name "unconnected-(CLK-~{CLK}-Pad5)") (class "Default")
      (node (ref "CLK") (pin "5") (pinfunction "~{CLK}_5") (pintype "output"))
    )
    (net (code "71") (name "unconnected-(CONV-PG-Pad8)") (class "Default")
      (node (ref "CONV") (pin "8") (pinfunction "PG_8") (pintype "bidirectional"))
    )
    (net (code "72") (name "unconnected-(IC1-NC1-Pad1)") (class "Default")
      (node (ref "IC1") (pin "1") (pinfunction "NC1_1") (pintype "no_connect"))
    )
    (net (code "73") (name "unconnected-(IC1-NC2-Pad2)") (class "Default")
      (node (ref "IC1") (pin "2") (pinfunction "NC2_2") (pintype "no_connect"))
    )
    (net (code "74") (name "unconnected-(IC1-NC3-Pad3)") (class "Default")
      (node (ref "IC1") (pin "3") (pinfunction "NC3_3") (pintype "no_connect"))
    )
    (net (code "75") (name "unconnected-(IC1-NC4-Pad7)") (class "Default")
      (node (ref "IC1") (pin "7") (pinfunction "NC4_7") (pintype "no_connect"))
    )
    (net (code "76") (name "unconnected-(IC3-B-Pad7)") (class "Default")
      (node (ref "IC3") (pin "7") (pinfunction "B_7") (pintype "bidirectional"))
    )
    (net (code "77") (name "unconnected-(SD-PadWP)") (class "Default")
      (node (ref "SD") (pin "WP") (pinfunction "WP_WP") (pintype "bidirectional"))
    )
    (net (code "78") (name "unconnected-(SR-Q'H-Pad9)") (class "Default")
      (node (ref "SR") (pin "9") (pinfunction "Q'H_9") (pintype "output"))
    )
    (net (code "79") (name "unconnected-(USB-PadD+)") (class "Default")
      (node (ref "USB") (pin "D+") (pinfunction "D+_D+") (pintype "bidirectional"))
    )
    (net (code "80") (name "unconnected-(USB-PadD-)") (class "Default")
      (node (ref "USB") (pin "D-") (pinfunction "D-_D-") (pintype "bidirectional"))
    )
  )
)
